# power.net
KiCad netlist of a schematic drawn in Altium Designer
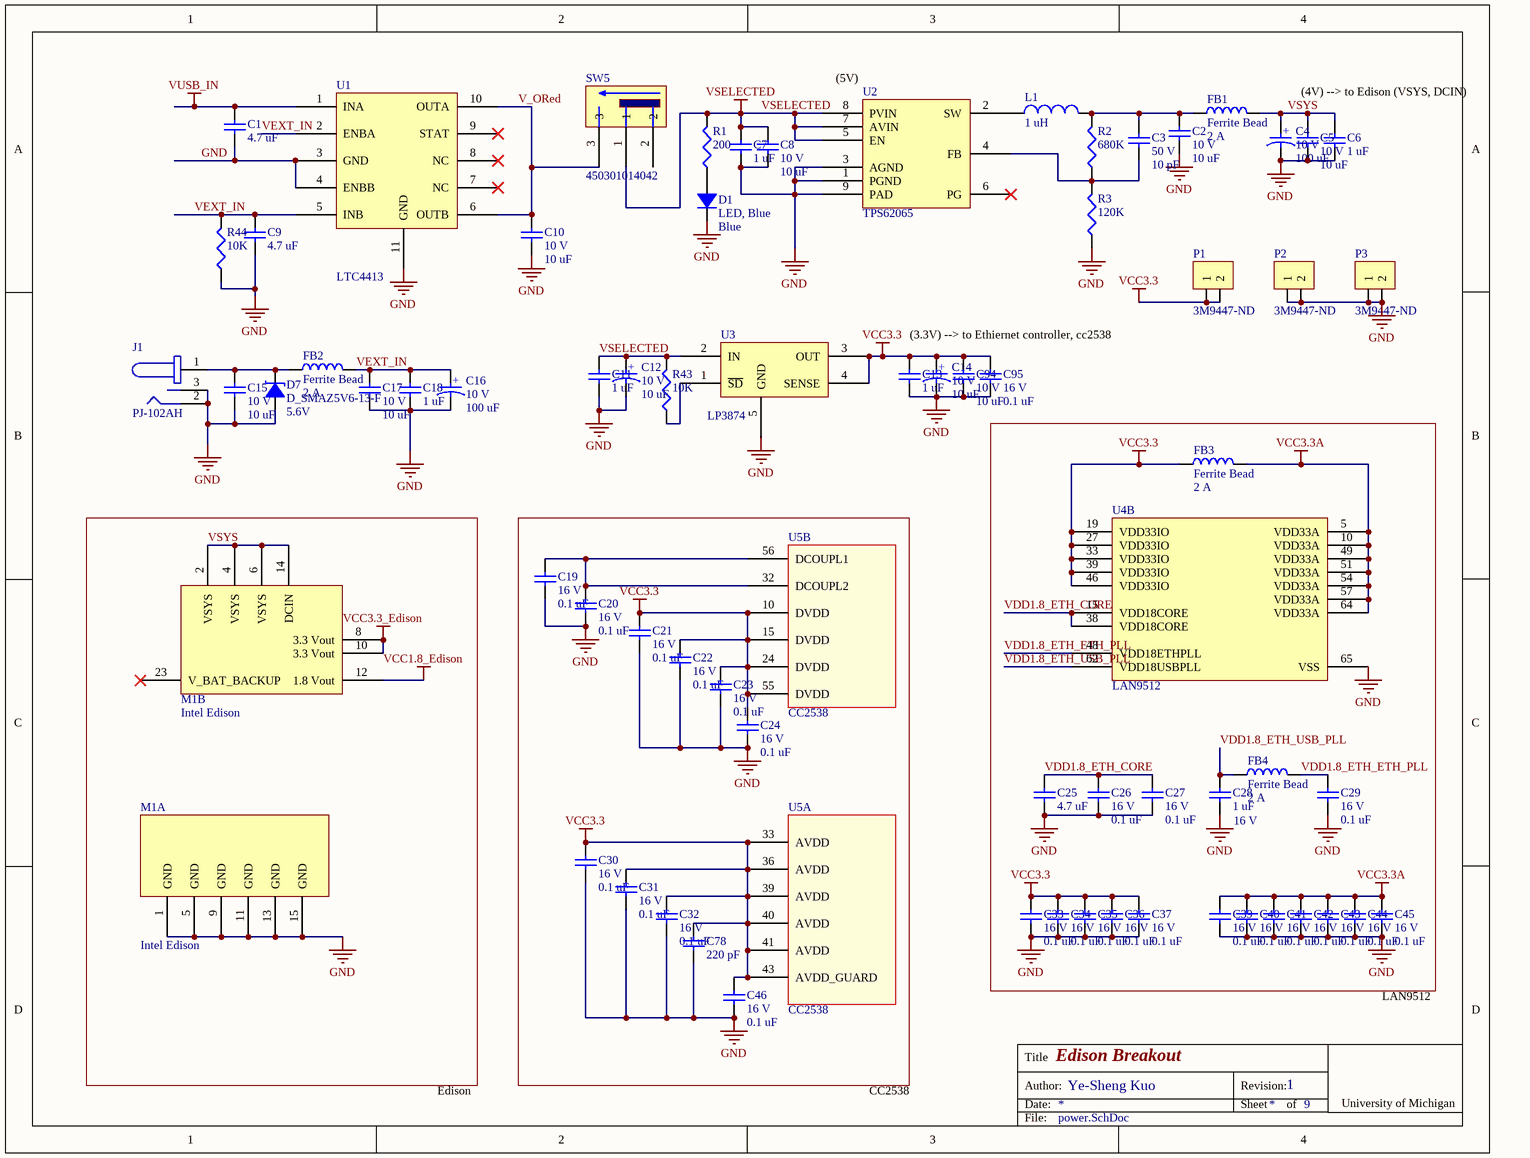
[diagram p0: power.SchDoc]

(export (version "E")
  (design (tool "Eeschema 10.0.6"))
  (components
    (comp (ref "C1")
      (value "4.7 uF")
      (footprint "0603")
      (description "Ceramic capacitor, 4.7u, 10V, 0603 package")
      (fields (field (name "TOLERANCE") "20%") (field (name "Comment") "Ceramic capacitor"))
      (libsource (lib "rlc") (part "C_4.7u_10V_0603_ceramic"))
    )
    (comp (ref "C2")
      (value "10 uF")
      (footprint "0603")
      (description "Ceramic capacitor, 10 uF, 10 V, 0603 package")
      (fields
        (field (name "TOLERANCE") "20%")
        (field (name "VOLTAGE RATED") "10 V")
        (field (name "Comment") "Ceramic capacitor")
      )
      (libsource (lib "rlc") (part "C_10u_10V_0603_ceramic"))
    )
    (comp (ref "C3")
      (value "10 pF")
      (footprint "0402")
      (description "Ceramic capacitor, 10 pF, 16 V, 0402 package")
      (fields
        (field (name "TOLERANCE") "1%")
        (field (name "VOLTAGE RATED") "50 V")
        (field (name "Comment") "Ceramic capacitor")
      )
      (libsource (lib "rlc") (part "C_10p_50V_0402_ceramic"))
    )
    (comp (ref "C4")
      (value "100 uF")
      (footprint "1206 - POLAR MARKING")
      (description "Tantalum capacitor, 100 uF, 10 V, 1206 package")
      (fields
        (field (name "TOLERANCE") "20%")
        (field (name "VOLTAGE RATED") "10 V")
        (field (name "Comment") "Tantalum capacitor")
      )
      (libsource (lib "rlc") (part "C_100u_10V_1206_tantalum"))
    )
    (comp (ref "C5")
      (value "10 uF")
      (footprint "0603")
      (description "Ceramic capacitor, 10 uF, 10 V, 0603 package")
      (fields
        (field (name "TOLERANCE") "20%")
        (field (name "VOLTAGE RATED") "10 V")
        (field (name "Comment") "Ceramic capacitor")
      )
      (libsource (lib "rlc") (part "C_10u_10V_0603_ceramic"))
    )
    (comp (ref "C6")
      (value "1 uF")
      (footprint "0402")
      (description "Ceramic capacitor, 1 uF, 16V, 0402 package")
      (fields (field (name "TOLERANCE") "10%") (field (name "Comment") "Ceramic capacitor"))
      (libsource (lib "rlc") (part "C_1u_16V_0402_ceramic"))
    )
    (comp (ref "C7")
      (value "1 uF")
      (footprint "0402")
      (description "Ceramic capacitor, 1 uF, 16V, 0402 package")
      (fields (field (name "TOLERANCE") "10%") (field (name "Comment") "Ceramic capacitor"))
      (libsource (lib "rlc") (part "C_1u_16V_0402_ceramic"))
    )
    (comp (ref "C8")
      (value "10 uF")
      (footprint "0603")
      (description "Ceramic capacitor, 10 uF, 10 V, 0603 package")
      (fields
        (field (name "TOLERANCE") "20%")
        (field (name "VOLTAGE RATED") "10 V")
        (field (name "Comment") "Ceramic capacitor")
      )
      (libsource (lib "rlc") (part "C_10u_10V_0603_ceramic"))
    )
    (comp (ref "C9")
      (value "4.7 uF")
      (footprint "0603")
      (description "Ceramic capacitor, 4.7u, 10V, 0603 package")
      (fields (field (name "TOLERANCE") "20%") (field (name "Comment") "Ceramic capacitor"))
      (libsource (lib "rlc") (part "C_4.7u_10V_0603_ceramic"))
    )
    (comp (ref "C10")
      (value "10 uF")
      (footprint "0603")
      (description "Ceramic capacitor, 10 uF, 10 V, 0603 package")
      (fields
        (field (name "TOLERANCE") "20%")
        (field (name "VOLTAGE RATED") "10 V")
        (field (name "Comment") "Ceramic capacitor")
      )
      (libsource (lib "rlc") (part "C_10u_10V_0603_ceramic"))
    )
    (comp (ref "C11")
      (value "1 uF")
      (footprint "0402")
      (description "Ceramic capacitor, 1 uF, 16V, 0402 package")
      (fields (field (name "TOLERANCE") "10%") (field (name "Comment") "Ceramic capacitor"))
      (libsource (lib "rlc") (part "C_1u_16V_0402_ceramic"))
    )
    (comp (ref "C12")
      (value "10 uF")
      (footprint "0603 - Polar Marking")
      (description "Tantalum capacitor, 10 uF, 10 V, 0603 package")
      (fields
        (field (name "TOLERANCE") "10%")
        (field (name "VOLTAGE RATED") "10 V")
        (field (name "Comment") "Tantalum capacitor")
      )
      (libsource (lib "rlc") (part "C_10u_10V_0603_tantalum"))
    )
    (comp (ref "C13")
      (value "1 uF")
      (footprint "0402")
      (description "Ceramic capacitor, 1 uF, 16V, 0402 package")
      (fields (field (name "TOLERANCE") "10%") (field (name "Comment") "Ceramic capacitor"))
      (libsource (lib "rlc") (part "C_1u_16V_0402_ceramic"))
    )
    (comp (ref "C14")
      (value "10 uF")
      (footprint "0603 - Polar Marking")
      (description "Tantalum capacitor, 10 uF, 10 V, 0603 package")
      (fields
        (field (name "TOLERANCE") "10%")
        (field (name "VOLTAGE RATED") "10 V")
        (field (name "Comment") "Tantalum capacitor")
      )
      (libsource (lib "rlc") (part "C_10u_10V_0603_tantalum"))
    )
    (comp (ref "C15")
      (value "10 uF")
      (footprint "0603")
      (description "Ceramic capacitor, 10 uF, 10 V, 0603 package")
      (fields
        (field (name "TOLERANCE") "20%")
        (field (name "VOLTAGE RATED") "10 V")
        (field (name "Comment") "Ceramic capacitor")
      )
      (libsource (lib "rlc") (part "C_10u_10V_0603_ceramic"))
    )
    (comp (ref "C16")
      (value "100 uF")
      (footprint "1206 - POLAR MARKING")
      (description "Tantalum capacitor, 100 uF, 10 V, 1206 package")
      (fields
        (field (name "TOLERANCE") "20%")
        (field (name "VOLTAGE RATED") "10 V")
        (field (name "Comment") "Tantalum capacitor")
      )
      (libsource (lib "rlc") (part "C_100u_10V_1206_tantalum"))
    )
    (comp (ref "C17")
      (value "10 uF")
      (footprint "0603")
      (description "Ceramic capacitor, 10 uF, 10 V, 0603 package")
      (fields
        (field (name "TOLERANCE") "20%")
        (field (name "VOLTAGE RATED") "10 V")
        (field (name "Comment") "Ceramic capacitor")
      )
      (libsource (lib "rlc") (part "C_10u_10V_0603_ceramic"))
    )
    (comp (ref "C18")
      (value "1 uF")
      (footprint "0402")
      (description "Ceramic capacitor, 1 uF, 16V, 0402 package")
      (fields (field (name "TOLERANCE") "10%") (field (name "Comment") "Ceramic capacitor"))
      (libsource (lib "rlc") (part "C_1u_16V_0402_ceramic"))
    )
    (comp (ref "C19")
      (value "0.1 uF")
      (footprint "0402")
      (description "Ceramic capacitor, 0.1u, 16 V, 0402 package")
      (fields
        (field (name "VOLTAGE RATED") "16 V")
        (field (name "TOLERANCE") "10%")
        (field (name "Comment") "Ceramic capacitor")
      )
      (libsource (lib "rlc") (part "C_0.1u_16V_0402_ceramic"))
    )
    (comp (ref "C20")
      (value "0.1 uF")
      (footprint "0402")
      (description "Ceramic capacitor, 0.1u, 16 V, 0402 package")
      (fields
        (field (name "VOLTAGE RATED") "16 V")
        (field (name "TOLERANCE") "10%")
        (field (name "Comment") "Ceramic capacitor")
      )
      (libsource (lib "rlc") (part "C_0.1u_16V_0402_ceramic"))
    )
    (comp (ref "C21")
      (value "0.1 uF")
      (footprint "0402")
      (description "Ceramic capacitor, 0.1u, 16 V, 0402 package")
      (fields
        (field (name "VOLTAGE RATED") "16 V")
        (field (name "TOLERANCE") "10%")
        (field (name "Comment") "Ceramic capacitor")
      )
      (libsource (lib "rlc") (part "C_0.1u_16V_0402_ceramic"))
    )
    (comp (ref "C22")
      (value "0.1 uF")
      (footprint "0402")
      (description "Ceramic capacitor, 0.1u, 16 V, 0402 package")
      (fields
        (field (name "VOLTAGE RATED") "16 V")
        (field (name "TOLERANCE") "10%")
        (field (name "Comment") "Ceramic capacitor")
      )
      (libsource (lib "rlc") (part "C_0.1u_16V_0402_ceramic"))
    )
    (comp (ref "C23")
      (value "0.1 uF")
      (footprint "0402")
      (description "Ceramic capacitor, 0.1u, 16 V, 0402 package")
      (fields
        (field (name "VOLTAGE RATED") "16 V")
        (field (name "TOLERANCE") "10%")
        (field (name "Comment") "Ceramic capacitor")
      )
      (libsource (lib "rlc") (part "C_0.1u_16V_0402_ceramic"))
    )
    (comp (ref "C24")
      (value "0.1 uF")
      (footprint "0402")
      (description "Ceramic capacitor, 0.1u, 16 V, 0402 package")
      (fields
        (field (name "VOLTAGE RATED") "16 V")
        (field (name "TOLERANCE") "10%")
        (field (name "Comment") "Ceramic capacitor")
      )
      (libsource (lib "rlc") (part "C_0.1u_16V_0402_ceramic"))
    )
    (comp (ref "C25")
      (value "4.7 uF")
      (footprint "0603")
      (description "Ceramic capacitor, 4.7u, 10V, 0603 package")
      (fields (field (name "TOLERANCE") "20%") (field (name "Comment") "Ceramic capacitor"))
      (libsource (lib "rlc") (part "C_4.7u_10V_0603_ceramic"))
    )
    (comp (ref "C26")
      (value "0.1 uF")
      (footprint "0402")
      (description "Ceramic capacitor, 0.1u, 16 V, 0402 package")
      (fields
        (field (name "VOLTAGE RATED") "16 V")
        (field (name "TOLERANCE") "10%")
        (field (name "Comment") "Ceramic capacitor")
      )
      (libsource (lib "rlc") (part "C_0.1u_16V_0402_ceramic"))
    )
    (comp (ref "C27")
      (value "0.1 uF")
      (footprint "0402")
      (description "Ceramic capacitor, 0.1u, 16 V, 0402 package")
      (fields
        (field (name "VOLTAGE RATED") "16 V")
        (field (name "TOLERANCE") "10%")
        (field (name "Comment") "Ceramic capacitor")
      )
      (libsource (lib "rlc") (part "C_0.1u_16V_0402_ceramic"))
    )
    (comp (ref "C28")
      (value "1 uF")
      (footprint "0402")
      (description "Ceramic capacitor, 1 uF, 16V, 0402 package")
      (fields
        (field (name "VOLTAGE RATED") "16 V")
        (field (name "TOLERANCE") "10%")
        (field (name "Comment") "Ceramic capacitor")
      )
      (libsource (lib "rlc") (part "C_1u_16V_0402_ceramic"))
    )
    (comp (ref "C29")
      (value "0.1 uF")
      (footprint "0402")
      (description "Ceramic capacitor, 0.1u, 16 V, 0402 package")
      (fields
        (field (name "VOLTAGE RATED") "16 V")
        (field (name "TOLERANCE") "10%")
        (field (name "Comment") "Ceramic capacitor")
      )
      (libsource (lib "rlc") (part "C_0.1u_16V_0402_ceramic"))
    )
    (comp (ref "C30")
      (value "0.1 uF")
      (footprint "0402")
      (description "Ceramic capacitor, 0.1u, 16 V, 0402 package")
      (fields
        (field (name "VOLTAGE RATED") "16 V")
        (field (name "TOLERANCE") "10%")
        (field (name "Comment") "Ceramic capacitor")
      )
      (libsource (lib "rlc") (part "C_0.1u_16V_0402_ceramic"))
    )
    (comp (ref "C31")
      (value "0.1 uF")
      (footprint "0402")
      (description "Ceramic capacitor, 0.1u, 16 V, 0402 package")
      (fields
        (field (name "VOLTAGE RATED") "16 V")
        (field (name "TOLERANCE") "10%")
        (field (name "Comment") "Ceramic capacitor")
      )
      (libsource (lib "rlc") (part "C_0.1u_16V_0402_ceramic"))
    )
    (comp (ref "C32")
      (value "0.1 uF")
      (footprint "0402")
      (description "Ceramic capacitor, 0.1u, 16 V, 0402 package")
      (fields
        (field (name "VOLTAGE RATED") "16 V")
        (field (name "TOLERANCE") "10%")
        (field (name "Comment") "Ceramic capacitor")
      )
      (libsource (lib "rlc") (part "C_0.1u_16V_0402_ceramic"))
    )
    (comp (ref "C33")
      (value "0.1 uF")
      (footprint "0402")
      (description "Ceramic capacitor, 0.1u, 16 V, 0402 package")
      (fields
        (field (name "VOLTAGE RATED") "16 V")
        (field (name "TOLERANCE") "10%")
        (field (name "Comment") "Ceramic capacitor")
      )
      (libsource (lib "rlc") (part "C_0.1u_16V_0402_ceramic"))
    )
    (comp (ref "C34")
      (value "0.1 uF")
      (footprint "0402")
      (description "Ceramic capacitor, 0.1u, 16 V, 0402 package")
      (fields
        (field (name "VOLTAGE RATED") "16 V")
        (field (name "TOLERANCE") "10%")
        (field (name "Comment") "Ceramic capacitor")
      )
      (libsource (lib "rlc") (part "C_0.1u_16V_0402_ceramic"))
    )
    (comp (ref "C35")
      (value "0.1 uF")
      (footprint "0402")
      (description "Ceramic capacitor, 0.1u, 16 V, 0402 package")
      (fields
        (field (name "VOLTAGE RATED") "16 V")
        (field (name "TOLERANCE") "10%")
        (field (name "Comment") "Ceramic capacitor")
      )
      (libsource (lib "rlc") (part "C_0.1u_16V_0402_ceramic"))
    )
    (comp (ref "C36")
      (value "0.1 uF")
      (footprint "0402")
      (description "Ceramic capacitor, 0.1u, 16 V, 0402 package")
      (fields
        (field (name "VOLTAGE RATED") "16 V")
        (field (name "TOLERANCE") "10%")
        (field (name "Comment") "Ceramic capacitor")
      )
      (libsource (lib "rlc") (part "C_0.1u_16V_0402_ceramic"))
    )
    (comp (ref "C37")
      (value "0.1 uF")
      (footprint "0402")
      (description "Ceramic capacitor, 0.1u, 16 V, 0402 package")
      (fields
        (field (name "VOLTAGE RATED") "16 V")
        (field (name "TOLERANCE") "10%")
        (field (name "Comment") "Ceramic capacitor")
      )
      (libsource (lib "rlc") (part "C_0.1u_16V_0402_ceramic"))
    )
    (comp (ref "C39")
      (value "0.1 uF")
      (footprint "0402")
      (description "Ceramic capacitor, 0.1u, 16 V, 0402 package")
      (fields
        (field (name "VOLTAGE RATED") "16 V")
        (field (name "TOLERANCE") "10%")
        (field (name "Comment") "Ceramic capacitor")
      )
      (libsource (lib "rlc") (part "C_0.1u_16V_0402_ceramic"))
    )
    (comp (ref "C40")
      (value "0.1 uF")
      (footprint "0402")
      (description "Ceramic capacitor, 0.1u, 16 V, 0402 package")
      (fields
        (field (name "VOLTAGE RATED") "16 V")
        (field (name "TOLERANCE") "10%")
        (field (name "Comment") "Ceramic capacitor")
      )
      (libsource (lib "rlc") (part "C_0.1u_16V_0402_ceramic"))
    )
    (comp (ref "C41")
      (value "0.1 uF")
      (footprint "0402")
      (description "Ceramic capacitor, 0.1u, 16 V, 0402 package")
      (fields
        (field (name "VOLTAGE RATED") "16 V")
        (field (name "TOLERANCE") "10%")
        (field (name "Comment") "Ceramic capacitor")
      )
      (libsource (lib "rlc") (part "C_0.1u_16V_0402_ceramic"))
    )
    (comp (ref "C42")
      (value "0.1 uF")
      (footprint "0402")
      (description "Ceramic capacitor, 0.1u, 16 V, 0402 package")
      (fields
        (field (name "VOLTAGE RATED") "16 V")
        (field (name "TOLERANCE") "10%")
        (field (name "Comment") "Ceramic capacitor")
      )
      (libsource (lib "rlc") (part "C_0.1u_16V_0402_ceramic"))
    )
    (comp (ref "C43")
      (value "0.1 uF")
      (footprint "0402")
      (description "Ceramic capacitor, 0.1u, 16 V, 0402 package")
      (fields
        (field (name "VOLTAGE RATED") "16 V")
        (field (name "TOLERANCE") "10%")
        (field (name "Comment") "Ceramic capacitor")
      )
      (libsource (lib "rlc") (part "C_0.1u_16V_0402_ceramic"))
    )
    (comp (ref "C44")
      (value "0.1 uF")
      (footprint "0402")
      (description "Ceramic capacitor, 0.1u, 16 V, 0402 package")
      (fields
        (field (name "VOLTAGE RATED") "16 V")
        (field (name "TOLERANCE") "10%")
        (field (name "Comment") "Ceramic capacitor")
      )
      (libsource (lib "rlc") (part "C_0.1u_16V_0402_ceramic"))
    )
    (comp (ref "C45")
      (value "0.1 uF")
      (footprint "0402")
      (description "Ceramic capacitor, 0.1u, 16 V, 0402 package")
      (fields
        (field (name "VOLTAGE RATED") "16 V")
        (field (name "TOLERANCE") "10%")
        (field (name "Comment") "Ceramic capacitor")
      )
      (libsource (lib "rlc") (part "C_0.1u_16V_0402_ceramic"))
    )
    (comp (ref "C46")
      (value "0.1 uF")
      (footprint "0402")
      (description "Ceramic capacitor, 0.1u, 16 V, 0402 package")
      (fields
        (field (name "VOLTAGE RATED") "16 V")
        (field (name "TOLERANCE") "10%")
        (field (name "Comment") "Ceramic capacitor")
      )
      (libsource (lib "rlc") (part "C_0.1u_16V_0402_ceramic"))
    )
    (comp (ref "C78")
      (value "220 pF")
      (footprint "0402")
      (description "Ceramic capacitor, 220 pF, 0402 package")
      (fields (field (name "TOLERANCE") "10%") (field (name "Comment") "Ceramic capacitor"))
      (libsource (lib "rlc") (part "C_220p_50V_0402_ceramic"))
    )
    (comp (ref "C94")
      (value "10 uF")
      (footprint "0603")
      (description "Ceramic capacitor, 10 uF, 10 V, 0603 package")
      (fields
        (field (name "TOLERANCE") "20%")
        (field (name "VOLTAGE RATED") "10 V")
        (field (name "Comment") "Ceramic capacitor")
      )
      (libsource (lib "rlc") (part "C_10u_10V_0603_ceramic"))
    )
    (comp (ref "C95")
      (value "0.1 uF")
      (footprint "0402")
      (description "Ceramic capacitor, 0.1u, 16 V, 0402 package")
      (fields
        (field (name "TOLERANCE") "10%")
        (field (name "VOLTAGE RATED") "16 V")
        (field (name "Comment") "Ceramic capacitor")
      )
      (libsource (lib "rlc") (part "C_0.1u_16V_0402_ceramic"))
    )
    (comp (ref "D1")
      (value "LED, Blue")
      (footprint "0402 - DIODE")
      (description "LED, Blue, 0402")
      (fields (field (name "COLOR") "Blue"))
      (libsource (lib "rlc") (part "D_LED_BLUE_0402"))
    )
    (comp (ref "D7")
      (value "D_SMAZ5V6-13-F")
      (footprint "SMAZ5V1")
      (description "SURFACE MOUNT ZENER DIODE")
      (fields (field (name "ZF") "5.6V"))
      (libsource (lib "rlc") (part "D_SMAZ5V6-13-F"))
    )
    (comp (ref "FB1")
      (value "Ferrite Bead")
      (footprint "0603")
      (description "Ferrite Bead, 2 A, 0603 package")
      (fields (field (name "CURRENT RATING") "2 A"))
      (libsource (lib "rlc") (part "FB_2A_0603"))
    )
    (comp (ref "FB2")
      (value "Ferrite Bead")
      (footprint "0603")
      (description "Ferrite Bead, 2 A, 0603 package")
      (fields (field (name "CURRENT RATING") "2 A"))
      (libsource (lib "rlc") (part "FB_2A_0603"))
    )
    (comp (ref "FB3")
      (value "Ferrite Bead")
      (footprint "0603")
      (description "Ferrite Bead, 2 A, 0603 package")
      (fields (field (name "CURRENT RATING") "2 A"))
      (libsource (lib "rlc") (part "FB_2A_0603"))
    )
    (comp (ref "FB4")
      (value "Ferrite Bead")
      (footprint "0603")
      (description "Ferrite Bead, 2 A, 0603 package")
      (fields (field (name "CURRENT RATING") "2 A"))
      (libsource (lib "rlc") (part "FB_2A_0603"))
    )
    (comp (ref "J1")
      (value "PJ-102AH")
      (footprint "PJ-102AH")
      (description "CONN PWR JACK 2.1X5.5MM HIGH CUR")
      (libsource (lib "connectors") (part "PJ-102AH"))
    )
    (comp (ref "L1")
      (value "1 uH")
      (footprint "1210")
      (description "Chip inductor, 1 uH, 1210 package, LQM32PN")
      (fields (field (name "TOLERANCE") "20%") (field (name "Comment") "Chip inductor"))
      (libsource (lib "rlc") (part "L_1u_LQM32PN"))
    )
    (comp (ref "M1")
      (value "Intel Edison")
      (footprint "Intel Edison mating")
      (libsource (lib "edison") (part "Intel Edison"))
    )
    (comp (ref "P1")
      (value "1 x 2 header")
      (footprint "1x2 header")
      (description "100 mils standard header")
      (fields (field (name "SUPPLIER PART NUMBER 1") "3M9447-ND"))
      (libsource (lib "connectors") (part "1 x 2 header"))
    )
    (comp (ref "P2")
      (value "1 x 2 header")
      (footprint "1x2 header")
      (description "100 mils standard header")
      (fields (field (name "SUPPLIER PART NUMBER 1") "3M9447-ND"))
      (libsource (lib "connectors") (part "1 x 2 header"))
    )
    (comp (ref "P3")
      (value "1 x 2 header")
      (footprint "1x2 header")
      (description "100 mils standard header")
      (fields (field (name "SUPPLIER PART NUMBER 1") "3M9447-ND"))
      (libsource (lib "connectors") (part "1 x 2 header"))
    )
    (comp (ref "R1")
      (value "200")
      (footprint "0402")
      (description "Chip resistor, 200, 0402 package")
      (fields (field (name "TOLERANCE") "1%") (field (name "POWER") "1/16 W"))
      (libsource (lib "rlc") (part "R_200_0402"))
    )
    (comp (ref "R2")
      (value "680K")
      (footprint "0402")
      (description "Chip resistor, 680K, 0402 package")
      (fields (field (name "TOLERANCE") "1%") (field (name "POWER") "1/16 W"))
      (libsource (lib "rlc") (part "R_680K_0402"))
    )
    (comp (ref "R3")
      (value "120K")
      (footprint "0402")
      (description "Chip resistor, 120K, 0402 package")
      (fields (field (name "TOLERANCE") "1%") (field (name "POWER") "1/16 W"))
      (libsource (lib "rlc") (part "R_120K_0402"))
    )
    (comp (ref "R43")
      (value "10K")
      (footprint "0402")
      (description "Chip resistor, 10K, 0402 package")
      (fields (field (name "TOLERANCE") "1%") (field (name "POWER") "1/16 W"))
      (libsource (lib "rlc") (part "R_10K_0402"))
    )
    (comp (ref "R44")
      (value "10K")
      (footprint "0402")
      (description "Chip resistor, 10K, 0402 package")
      (fields (field (name "TOLERANCE") "1%") (field (name "POWER") "1/16 W"))
      (libsource (lib "rlc") (part "R_10K_0402"))
    )
    (comp (ref "SW5")
      (value "450301014042")
      (footprint "450301014042")
      (description "Slide switch, SPDT, 500 mA, 12 V")
      (libsource (lib "switches") (part "450301014042"))
    )
    (comp (ref "U1")
      (value "LTC4413")
      (footprint "DFN-10")
      (description "Dual 2.6A, 2.5V to 5.5V,  Ideal Diodes in 3mm × 3mm DFN")
      (libsource (lib "powerpath_selector") (part "LTC4413"))
    )
    (comp (ref "U2")
      (value "TPS62065")
      (footprint "PWSON-8")
      (description "3-MHz, 2-A, Step-Down Converter")
      (libsource (lib "voltage_regulators") (part "TPS62065"))
    )
    (comp (ref "U3")
      (value "LP3874")
      (footprint "SOT150P700X180-5N")
      (description "LP387x 0.8-A Fast Ultra-Low-Dropout Linear Regulators")
      (libsource (lib "voltage_regulators") (part "LP3874"))
    )
    (comp (ref "U4")
      (value "LAN9512")
      (footprint "QFN-64")
      (description "USB 2.0 Hub and 10/100  Ethernet Controller")
      (libsource (lib "ethernet") (part "LAN9512"))
    )
    (comp (ref "U5")
      (value "CC2538")
      (footprint "QFN56")
      (description "A Powerful System-On-Chip for 2.4-GHz IEEE 802.15.4, 6LoWPAN  and ZigBee Applications")
      (libsource (lib "mcu") (part "CC2538"))
    )
  )
  (nets
    (net (code "1") (name "/VDD1.8_ETH_CORE") (class "Default")
      (node (ref "C25") (pin "1") (pintype "passive"))
      (node (ref "C26") (pin "1") (pintype "passive"))
      (node (ref "C27") (pin "1") (pintype "passive"))
      (node (ref "U4") (pin "15") (pinfunction "VDD18CORE_15") (pintype "passive"))
      (node (ref "U4") (pin "38") (pinfunction "VDD18CORE_38") (pintype "passive"))
    )
    (net (code "2") (name "/VDD1.8_ETH_ETH_PLL") (class "Default")
      (node (ref "C29") (pin "1") (pintype "passive"))
      (node (ref "FB4") (pin "1") (pintype "passive"))
      (node (ref "U4") (pin "48") (pinfunction "VDD18ETHPLL_48") (pintype "passive"))
    )
    (net (code "3") (name "/VDD1.8_ETH_USB_PLL") (class "Default")
      (node (ref "C28") (pin "1") (pintype "passive"))
      (node (ref "FB4") (pin "2") (pintype "passive"))
      (node (ref "U4") (pin "62") (pinfunction "VDD18USBPLL_62") (pintype "passive"))
    )
    (net (code "4") (name "/VEXT_IN") (class "Default")
      (node (ref "C16") (pin "1") (pintype "passive"))
      (node (ref "C17") (pin "1") (pintype "passive"))
      (node (ref "C18") (pin "1") (pintype "passive"))
      (node (ref "C9") (pin "1") (pintype "passive"))
      (node (ref "FB2") (pin "1") (pintype "passive"))
      (node (ref "R44") (pin "1") (pintype "passive"))
      (node (ref "U1") (pin "2") (pinfunction "ENBA_2") (pintype "passive"))
      (node (ref "U1") (pin "5") (pinfunction "INB_5") (pintype "passive"))
    )
    (net (code "5") (name "/VSYS") (class "Default")
      (node (ref "C4") (pin "1") (pintype "passive"))
      (node (ref "C5") (pin "1") (pintype "passive"))
      (node (ref "C6") (pin "1") (pintype "passive"))
      (node (ref "FB1") (pin "1") (pintype "passive"))
      (node (ref "M1") (pin "14") (pinfunction "DCIN_14") (pintype "passive"))
      (node (ref "M1") (pin "2") (pinfunction "VSYS_2") (pintype "passive"))
      (node (ref "M1") (pin "4") (pinfunction "VSYS_4") (pintype "passive"))
      (node (ref "M1") (pin "6") (pinfunction "VSYS_6") (pintype "passive"))
    )
    (net (code "6") (name "/V_ORed") (class "Default")
      (node (ref "C10") (pin "1") (pintype "passive"))
      (node (ref "SW5") (pin "3") (pinfunction "3_3") (pintype "passive"))
      (node (ref "U1") (pin "10") (pinfunction "OUTA_10") (pintype "passive"))
      (node (ref "U1") (pin "6") (pinfunction "OUTB_6") (pintype "passive"))
    )
    (net (code "7") (name "GND") (class "Default")
      (node (ref "C1") (pin "2") (pintype "passive"))
      (node (ref "C10") (pin "2") (pintype "passive"))
      (node (ref "C11") (pin "2") (pintype "passive"))
      (node (ref "C12") (pin "2") (pintype "passive"))
      (node (ref "C13") (pin "2") (pintype "passive"))
      (node (ref "C14") (pin "2") (pintype "passive"))
      (node (ref "C15") (pin "2") (pintype "passive"))
      (node (ref "C16") (pin "2") (pintype "passive"))
      (node (ref "C17") (pin "2") (pintype "passive"))
      (node (ref "C18") (pin "2") (pintype "passive"))
      (node (ref "C19") (pin "2") (pintype "passive"))
      (node (ref "C2") (pin "2") (pintype "passive"))
      (node (ref "C20") (pin "2") (pintype "passive"))
      (node (ref "C21") (pin "2") (pintype "passive"))
      (node (ref "C22") (pin "2") (pintype "passive"))
      (node (ref "C23") (pin "2") (pintype "passive"))
      (node (ref "C24") (pin "2") (pintype "passive"))
      (node (ref "C25") (pin "2") (pintype "passive"))
      (node (ref "C26") (pin "2") (pintype "passive"))
      (node (ref "C27") (pin "2") (pintype "passive"))
      (node (ref "C28") (pin "2") (pintype "passive"))
      (node (ref "C29") (pin "2") (pintype "passive"))
      (node (ref "C30") (pin "2") (pintype "passive"))
      (node (ref "C31") (pin "2") (pintype "passive"))
      (node (ref "C32") (pin "2") (pintype "passive"))
      (node (ref "C33") (pin "2") (pintype "passive"))
      (node (ref "C34") (pin "2") (pintype "passive"))
      (node (ref "C35") (pin "2") (pintype "passive"))
      (node (ref "C36") (pin "2") (pintype "passive"))
      (node (ref "C37") (pin "2") (pintype "passive"))
      (node (ref "C39") (pin "2") (pintype "passive"))
      (node (ref "C4") (pin "2") (pintype "passive"))
      (node (ref "C40") (pin "2") (pintype "passive"))
      (node (ref "C41") (pin "2") (pintype "passive"))
      (node (ref "C42") (pin "2") (pintype "passive"))
      (node (ref "C43") (pin "2") (pintype "passive"))
      (node (ref "C44") (pin "2") (pintype "passive"))
      (node (ref "C45") (pin "2") (pintype "passive"))
      (node (ref "C46") (pin "2") (pintype "passive"))
      (node (ref "C5") (pin "2") (pintype "passive"))
      (node (ref "C6") (pin "2") (pintype "passive"))
      (node (ref "C7") (pin "2") (pintype "passive"))
      (node (ref "C78") (pin "2") (pintype "passive"))
      (node (ref "C8") (pin "2") (pintype "passive"))
      (node (ref "C9") (pin "2") (pintype "passive"))
      (node (ref "C94") (pin "2") (pintype "passive"))
      (node (ref "C95") (pin "2") (pintype "passive"))
      (node (ref "D1") (pin "2") (pintype "passive"))
      (node (ref "D7") (pin "1") (pintype "passive"))
      (node (ref "J1") (pin "2") (pintype "passive"))
      (node (ref "J1") (pin "3") (pintype "passive"))
      (node (ref "M1") (pin "1") (pinfunction "GND_1") (pintype "passive"))
      (node (ref "M1") (pin "11") (pinfunction "GND_11") (pintype "passive"))
      (node (ref "M1") (pin "13") (pinfunction "GND_13") (pintype "passive"))
      (node (ref "M1") (pin "15") (pinfunction "GND_15") (pintype "passive"))
      (node (ref "M1") (pin "5") (pinfunction "GND_5") (pintype "passive"))
      (node (ref "M1") (pin "9") (pinfunction "GND_9") (pintype "passive"))
      (node (ref "P2") (pin "1") (pinfunction "1_1") (pintype "passive"))
      (node (ref "P2") (pin "2") (pinfunction "2_2") (pintype "passive"))
      (node (ref "P3") (pin "1") (pinfunction "1_1") (pintype "passive"))
      (node (ref "P3") (pin "2") (pinfunction "2_2") (pintype "passive"))
      (node (ref "R3") (pin "2") (pintype "passive"))
      (node (ref "R44") (pin "2") (pintype "passive"))
      (node (ref "U1") (pin "11") (pinfunction "GND_11") (pintype "passive"))
      (node (ref "U1") (pin "3") (pinfunction "GND_3") (pintype "passive"))
      (node (ref "U1") (pin "4") (pinfunction "ENBB_4") (pintype "passive"))
      (node (ref "U2") (pin "1") (pinfunction "PGND_1") (pintype "passive"))
      (node (ref "U2") (pin "3") (pinfunction "AGND_3") (pintype "passive"))
      (node (ref "U2") (pin "9") (pinfunction "PAD_9") (pintype "passive"))
      (node (ref "U3") (pin "5") (pinfunction "GND_5") (pintype "passive"))
      (node (ref "U4") (pin "65") (pinfunction "VSS_65") (pintype "passive"))
    )
    (net (code "8") (name "Net-(C2-Pad1)") (class "Default")
      (node (ref "C2") (pin "1") (pintype "passive"))
      (node (ref "C3") (pin "1") (pintype "passive"))
      (node (ref "FB1") (pin "2") (pintype "passive"))
      (node (ref "L1") (pin "1") (pintype "passive"))
      (node (ref "R2") (pin "1") (pintype "passive"))
    )
    (net (code "9") (name "Net-(C15-Pad1)") (class "Default")
      (node (ref "C15") (pin "1") (pintype "passive"))
      (node (ref "D7") (pin "2") (pintype "passive"))
      (node (ref "FB2") (pin "2") (pintype "passive"))
      (node (ref "J1") (pin "1") (pintype "passive"))
    )
    (net (code "10") (name "Net-(D1-Pad1)") (class "Default")
      (node (ref "D1") (pin "1") (pintype "passive"))
      (node (ref "R1") (pin "2") (pintype "passive"))
    )
    (net (code "11") (name "Net-(U2-FB)") (class "Default")
      (node (ref "C3") (pin "2") (pintype "passive"))
      (node (ref "R2") (pin "2") (pintype "passive"))
      (node (ref "R3") (pin "1") (pintype "passive"))
      (node (ref "U2") (pin "4") (pinfunction "FB_4") (pintype "passive"))
    )
    (net (code "12") (name "Net-(U2-SW)") (class "Default")
      (node (ref "L1") (pin "2") (pintype "passive"))
      (node (ref "U2") (pin "2") (pinfunction "SW_2") (pintype "passive"))
    )
    (net (code "13") (name "Net-(U3-~{SD})") (class "Default")
      (node (ref "R43") (pin "2") (pintype "passive"))
      (node (ref "U3") (pin "1") (pinfunction "~{SD}_1") (pintype "passive"))
    )
    (net (code "14") (name "Net-(U5B-DCOUPL1)") (class "Default")
      (node (ref "C19") (pin "1") (pintype "passive"))
      (node (ref "C20") (pin "1") (pintype "passive"))
      (node (ref "U5") (pin "32") (pinfunction "DCOUPL2_32") (pintype "power_in"))
      (node (ref "U5") (pin "56") (pinfunction "DCOUPL1_56") (pintype "power_in"))
    )
    (net (code "15") (name "VCC1.8_Edison") (class "Default")
      (node (ref "M1") (pin "12") (pinfunction "1.8_Vout_12") (pintype "power_in"))
    )
    (net (code "16") (name "VCC3.3") (class "Default")
      (node (ref "C13") (pin "1") (pintype "passive"))
      (node (ref "C14") (pin "1") (pintype "passive"))
      (node (ref "C21") (pin "1") (pintype "passive"))
      (node (ref "C22") (pin "1") (pintype "passive"))
      (node (ref "C23") (pin "1") (pintype "passive"))
      (node (ref "C24") (pin "1") (pintype "passive"))
      (node (ref "C30") (pin "1") (pintype "passive"))
      (node (ref "C31") (pin "1") (pintype "passive"))
      (node (ref "C32") (pin "1") (pintype "passive"))
      (node (ref "C33") (pin "1") (pintype "passive"))
      (node (ref "C34") (pin "1") (pintype "passive"))
      (node (ref "C35") (pin "1") (pintype "passive"))
      (node (ref "C36") (pin "1") (pintype "passive"))
      (node (ref "C37") (pin "1") (pintype "passive"))
      (node (ref "C46") (pin "1") (pintype "passive"))
      (node (ref "C78") (pin "1") (pintype "passive"))
      (node (ref "C94") (pin "1") (pintype "passive"))
      (node (ref "C95") (pin "1") (pintype "passive"))
      (node (ref "FB3") (pin "2") (pintype "passive"))
      (node (ref "P1") (pin "1") (pinfunction "1_1") (pintype "passive"))
      (node (ref "P1") (pin "2") (pinfunction "2_2") (pintype "passive"))
      (node (ref "U3") (pin "3") (pinfunction "OUT_3") (pintype "passive"))
      (node (ref "U3") (pin "4") (pinfunction "SENSE_4") (pintype "passive"))
      (node (ref "U4") (pin "19") (pinfunction "VDD33IO_19") (pintype "passive"))
      (node (ref "U4") (pin "27") (pinfunction "VDD33IO_27") (pintype "passive"))
      (node (ref "U4") (pin "33") (pinfunction "VDD33IO_33") (pintype "passive"))
      (node (ref "U4") (pin "39") (pinfunction "VDD33IO_39") (pintype "passive"))
      (node (ref "U4") (pin "46") (pinfunction "VDD33IO_46") (pintype "passive"))
      (node (ref "U5") (pin "10") (pinfunction "DVDD_10") (pintype "power_in"))
      (node (ref "U5") (pin "15") (pinfunction "DVDD_15") (pintype "power_in"))
      (node (ref "U5") (pin "24") (pinfunction "DVDD_24") (pintype "power_in"))
      (node (ref "U5") (pin "33") (pinfunction "AVDD_33") (pintype "power_in"))
      (node (ref "U5") (pin "36") (pinfunction "AVDD_36") (pintype "power_in"))
      (node (ref "U5") (pin "39") (pinfunction "AVDD_39") (pintype "power_in"))
      (node (ref "U5") (pin "40") (pinfunction "AVDD_40") (pintype "power_in"))
      (node (ref "U5") (pin "41") (pinfunction "AVDD_41") (pintype "power_in"))
      (node (ref "U5") (pin "43") (pinfunction "AVDD_GUARD_43") (pintype "power_in"))
      (node (ref "U5") (pin "55") (pinfunction "DVDD_55") (pintype "power_in"))
    )
    (net (code "17") (name "VCC3.3A") (class "Default")
      (node (ref "C39") (pin "1") (pintype "passive"))
      (node (ref "C40") (pin "1") (pintype "passive"))
      (node (ref "C41") (pin "1") (pintype "passive"))
      (node (ref "C42") (pin "1") (pintype "passive"))
      (node (ref "C43") (pin "1") (pintype "passive"))
      (node (ref "C44") (pin "1") (pintype "passive"))
      (node (ref "C45") (pin "1") (pintype "passive"))
      (node (ref "FB3") (pin "1") (pintype "passive"))
      (node (ref "U4") (pin "10") (pinfunction "VDD33A_10") (pintype "passive"))
      (node (ref "U4") (pin "49") (pinfunction "VDD33A_49") (pintype "passive"))
      (node (ref "U4") (pin "5") (pinfunction "VDD33A_5") (pintype "passive"))
      (node (ref "U4") (pin "51") (pinfunction "VDD33A_51") (pintype "passive"))
      (node (ref "U4") (pin "54") (pinfunction "VDD33A_54") (pintype "passive"))
      (node (ref "U4") (pin "57") (pinfunction "VDD33A_57") (pintype "passive"))
      (node (ref "U4") (pin "64") (pinfunction "VDD33A_64") (pintype "passive"))
    )
    (net (code "18") (name "VCC3.3_Edison") (class "Default")
      (node (ref "M1") (pin "10") (pinfunction "3.3_Vout_10") (pintype "power_in"))
      (node (ref "M1") (pin "8") (pinfunction "3.3_Vout_8") (pintype "power_in"))
    )
    (net (code "19") (name "VSELECTED") (class "Default")
      (node (ref "C11") (pin "1") (pintype "passive"))
      (node (ref "C12") (pin "1") (pintype "passive"))
      (node (ref "C7") (pin "1") (pintype "passive"))
      (node (ref "C8") (pin "1") (pintype "passive"))
      (node (ref "R1") (pin "1") (pintype "passive"))
      (node (ref "R43") (pin "1") (pintype "passive"))
      (node (ref "SW5") (pin "1") (pinfunction "1_1") (pintype "passive"))
      (node (ref "U2") (pin "5") (pinfunction "EN_5") (pintype "passive"))
      (node (ref "U2") (pin "7") (pinfunction "AVIN_7") (pintype "passive"))
      (node (ref "U2") (pin "8") (pinfunction "PVIN_8") (pintype "passive"))
      (node (ref "U3") (pin "2") (pinfunction "IN_2") (pintype "passive"))
    )
    (net (code "20") (name "VUSB_IN") (class "Default")
      (node (ref "C1") (pin "1") (pintype "passive"))
      (node (ref "U1") (pin "1") (pinfunction "INA_1") (pintype "passive"))
    )
    (net (code "21") (name "unconnected-(M1B-V_BAT_BACKUP-Pad23)") (class "Default")
      (node (ref "M1") (pin "23") (pinfunction "V_BAT_BACKUP_23") (pintype "power_in+no_connect"))
    )
    (net (code "22") (name "unconnected-(SW5-Pad2)") (class "Default")
      (node (ref "SW5") (pin "2") (pinfunction "2_2") (pintype "passive"))
    )
    (net (code "23") (name "unconnected-(U1-NC-Pad7)") (class "Default")
      (node (ref "U1") (pin "7") (pinfunction "NC_7") (pintype "passive+no_connect"))
    )
    (net (code "24") (name "unconnected-(U1-NC-Pad8)") (class "Default")
      (node (ref "U1") (pin "8") (pinfunction "NC_8") (pintype "passive+no_connect"))
    )
    (net (code "25") (name "unconnected-(U1-STAT-Pad9)") (class "Default")
      (node (ref "U1") (pin "9") (pinfunction "STAT_9") (pintype "passive+no_connect"))
    )
    (net (code "26") (name "unconnected-(U2-PG-Pad6)") (class "Default")
      (node (ref "U2") (pin "6") (pinfunction "PG_6") (pintype "passive+no_connect"))
    )
  )
)
